# Digital_Port_F_Button.net
KiCad netlist of a schematic drawn in Altium Designer
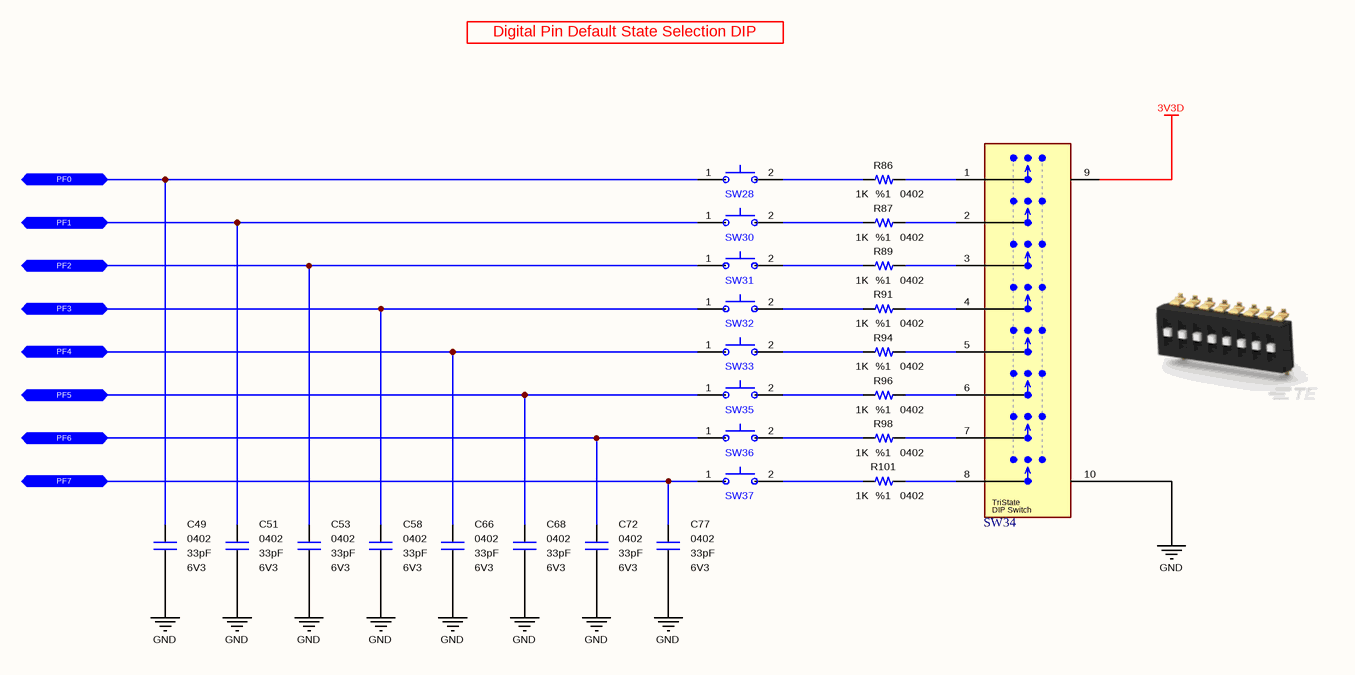
[diagram p0: Digital Port F Button.SchDoc]

(export (version "E")
  (design (tool "Eeschema 10.0.6"))
  (components
    (comp (ref "C49")
      (value "33pF")
      (footprint "CAPACITOR_0402")
      (description "Capacitor - 33pF [0402] (Ceramic)")
      (fields
        (field (name "MANUFACTURER PART NUMBER") "C0402C330J9RACAUTO")
        (field (name "MOUSER PART NUMBER") "80-C0402C330J9RAUTO")
        (field (name "CASE") "0402")
        (field (name "VOLTAGE") "6V3")
      )
      (libsource (lib "Ovoo_Library") (part "Capacitor - 33pF [0402-6V3]"))
    )
    (comp (ref "C51")
      (value "33pF")
      (footprint "CAPACITOR_0402")
      (description "Capacitor - 33pF [0402] (Ceramic)")
      (fields
        (field (name "MANUFACTURER PART NUMBER") "C0402C330J9RACAUTO")
        (field (name "MOUSER PART NUMBER") "80-C0402C330J9RAUTO")
        (field (name "CASE") "0402")
        (field (name "VOLTAGE") "6V3")
      )
      (libsource (lib "Ovoo_Library") (part "Capacitor - 33pF [0402-6V3]"))
    )
    (comp (ref "C53")
      (value "33pF")
      (footprint "CAPACITOR_0402")
      (description "Capacitor - 33pF [0402] (Ceramic)")
      (fields
        (field (name "MANUFACTURER PART NUMBER") "C0402C330J9RACAUTO")
        (field (name "MOUSER PART NUMBER") "80-C0402C330J9RAUTO")
        (field (name "CASE") "0402")
        (field (name "VOLTAGE") "6V3")
      )
      (libsource (lib "Ovoo_Library") (part "Capacitor - 33pF [0402-6V3]"))
    )
    (comp (ref "C58")
      (value "33pF")
      (footprint "CAPACITOR_0402")
      (description "Capacitor - 33pF [0402] (Ceramic)")
      (fields
        (field (name "MANUFACTURER PART NUMBER") "C0402C330J9RACAUTO")
        (field (name "MOUSER PART NUMBER") "80-C0402C330J9RAUTO")
        (field (name "CASE") "0402")
        (field (name "VOLTAGE") "6V3")
      )
      (libsource (lib "Ovoo_Library") (part "Capacitor - 33pF [0402-6V3]"))
    )
    (comp (ref "C66")
      (value "33pF")
      (footprint "CAPACITOR_0402")
      (description "Capacitor - 33pF [0402] (Ceramic)")
      (fields
        (field (name "MANUFACTURER PART NUMBER") "C0402C330J9RACAUTO")
        (field (name "MOUSER PART NUMBER") "80-C0402C330J9RAUTO")
        (field (name "CASE") "0402")
        (field (name "VOLTAGE") "6V3")
      )
      (libsource (lib "Ovoo_Library") (part "Capacitor - 33pF [0402-6V3]"))
    )
    (comp (ref "C68")
      (value "33pF")
      (footprint "CAPACITOR_0402")
      (description "Capacitor - 33pF [0402] (Ceramic)")
      (fields
        (field (name "MANUFACTURER PART NUMBER") "C0402C330J9RACAUTO")
        (field (name "MOUSER PART NUMBER") "80-C0402C330J9RAUTO")
        (field (name "CASE") "0402")
        (field (name "VOLTAGE") "6V3")
      )
      (libsource (lib "Ovoo_Library") (part "Capacitor - 33pF [0402-6V3]"))
    )
    (comp (ref "C72")
      (value "33pF")
      (footprint "CAPACITOR_0402")
      (description "Capacitor - 33pF [0402] (Ceramic)")
      (fields
        (field (name "MANUFACTURER PART NUMBER") "C0402C330J9RACAUTO")
        (field (name "MOUSER PART NUMBER") "80-C0402C330J9RAUTO")
        (field (name "CASE") "0402")
        (field (name "VOLTAGE") "6V3")
      )
      (libsource (lib "Ovoo_Library") (part "Capacitor - 33pF [0402-6V3]"))
    )
    (comp (ref "C77")
      (value "33pF")
      (footprint "CAPACITOR_0402")
      (description "Capacitor - 33pF [0402] (Ceramic)")
      (fields
        (field (name "MANUFACTURER PART NUMBER") "C0402C330J9RACAUTO")
        (field (name "MOUSER PART NUMBER") "80-C0402C330J9RAUTO")
        (field (name "CASE") "0402")
        (field (name "VOLTAGE") "6V3")
      )
      (libsource (lib "Ovoo_Library") (part "Capacitor - 33pF [0402-6V3]"))
    )
    (comp (ref "R86")
      (value "1K")
      (footprint "RESISTOR_0402")
      (description "Thick Film Resistors - SMD 1/16 W 1.0 Kohms 1%")
      (fields
        (field (name "MANUFACTURER PART NUMBER") "CRCW04021K00FKED")
        (field (name "MOUSER PART NUMBER") "71-CRCW0402-1.0K-E3")
        (field (name "TOLERANCE") "%1")
        (field (name "CASE") "0402")
      )
      (libsource (lib "Ovoo_Library") (part "Resistor - 1K"))
    )
    (comp (ref "R87")
      (value "1K")
      (footprint "RESISTOR_0402")
      (description "Thick Film Resistors - SMD 1/16 W 1.0 Kohms 1%")
      (fields
        (field (name "MANUFACTURER PART NUMBER") "CRCW04021K00FKED")
        (field (name "MOUSER PART NUMBER") "71-CRCW0402-1.0K-E3")
        (field (name "TOLERANCE") "%1")
        (field (name "CASE") "0402")
      )
      (libsource (lib "Ovoo_Library") (part "Resistor - 1K"))
    )
    (comp (ref "R89")
      (value "1K")
      (footprint "RESISTOR_0402")
      (description "Thick Film Resistors - SMD 1/16 W 1.0 Kohms 1%")
      (fields
        (field (name "MANUFACTURER PART NUMBER") "CRCW04021K00FKED")
        (field (name "MOUSER PART NUMBER") "71-CRCW0402-1.0K-E3")
        (field (name "TOLERANCE") "%1")
        (field (name "CASE") "0402")
      )
      (libsource (lib "Ovoo_Library") (part "Resistor - 1K"))
    )
    (comp (ref "R91")
      (value "1K")
      (footprint "RESISTOR_0402")
      (description "Thick Film Resistors - SMD 1/16 W 1.0 Kohms 1%")
      (fields
        (field (name "MANUFACTURER PART NUMBER") "CRCW04021K00FKED")
        (field (name "MOUSER PART NUMBER") "71-CRCW0402-1.0K-E3")
        (field (name "TOLERANCE") "%1")
        (field (name "CASE") "0402")
      )
      (libsource (lib "Ovoo_Library") (part "Resistor - 1K"))
    )
    (comp (ref "R94")
      (value "1K")
      (footprint "RESISTOR_0402")
      (description "Thick Film Resistors - SMD 1/16 W 1.0 Kohms 1%")
      (fields
        (field (name "MANUFACTURER PART NUMBER") "CRCW04021K00FKED")
        (field (name "MOUSER PART NUMBER") "71-CRCW0402-1.0K-E3")
        (field (name "TOLERANCE") "%1")
        (field (name "CASE") "0402")
      )
      (libsource (lib "Ovoo_Library") (part "Resistor - 1K"))
    )
    (comp (ref "R96")
      (value "1K")
      (footprint "RESISTOR_0402")
      (description "Thick Film Resistors - SMD 1/16 W 1.0 Kohms 1%")
      (fields
        (field (name "MANUFACTURER PART NUMBER") "CRCW04021K00FKED")
        (field (name "MOUSER PART NUMBER") "71-CRCW0402-1.0K-E3")
        (field (name "TOLERANCE") "%1")
        (field (name "CASE") "0402")
      )
      (libsource (lib "Ovoo_Library") (part "Resistor - 1K"))
    )
    (comp (ref "R98")
      (value "1K")
      (footprint "RESISTOR_0402")
      (description "Thick Film Resistors - SMD 1/16 W 1.0 Kohms 1%")
      (fields
        (field (name "MANUFACTURER PART NUMBER") "CRCW04021K00FKED")
        (field (name "MOUSER PART NUMBER") "71-CRCW0402-1.0K-E3")
        (field (name "TOLERANCE") "%1")
        (field (name "CASE") "0402")
      )
      (libsource (lib "Ovoo_Library") (part "Resistor - 1K"))
    )
    (comp (ref "R101")
      (value "1K")
      (footprint "RESISTOR_0402")
      (description "Thick Film Resistors - SMD 1/16 W 1.0 Kohms 1%")
      (fields
        (field (name "MANUFACTURER PART NUMBER") "CRCW04021K00FKED")
        (field (name "MOUSER PART NUMBER") "71-CRCW0402-1.0K-E3")
        (field (name "TOLERANCE") "%1")
        (field (name "CASE") "0402")
      )
      (libsource (lib "Ovoo_Library") (part "Resistor - 1K"))
    )
    (comp (ref "SW28")
      (value "Tactile Switches")
      (footprint "PTS526_Switch")
      (description "Tactile Switches 50mA 12VDC, 5.2x5.2mm, 0.8mm H, 260gf, G leads.")
      (fields
        (field (name "MANUFACTURER PART NUMBER") "PTS526 SK08 SMTR2 LFS")
        (field (name "MOUSER PART NUMBER") "611-PTS526SK08SMTR2L")
      )
      (libsource (lib "Ovoo_Library") (part "Switch - Tactile"))
    )
    (comp (ref "SW30")
      (value "Tactile Switches")
      (footprint "PTS526_Switch")
      (description "Tactile Switches 50mA 12VDC, 5.2x5.2mm, 0.8mm H, 260gf, G leads.")
      (fields
        (field (name "MANUFACTURER PART NUMBER") "PTS526 SK08 SMTR2 LFS")
        (field (name "MOUSER PART NUMBER") "611-PTS526SK08SMTR2L")
      )
      (libsource (lib "Ovoo_Library") (part "Switch - Tactile"))
    )
    (comp (ref "SW31")
      (value "Tactile Switches")
      (footprint "PTS526_Switch")
      (description "Tactile Switches 50mA 12VDC, 5.2x5.2mm, 0.8mm H, 260gf, G leads.")
      (fields
        (field (name "MANUFACTURER PART NUMBER") "PTS526 SK08 SMTR2 LFS")
        (field (name "MOUSER PART NUMBER") "611-PTS526SK08SMTR2L")
      )
      (libsource (lib "Ovoo_Library") (part "Switch - Tactile"))
    )
    (comp (ref "SW32")
      (value "Tactile Switches")
      (footprint "PTS526_Switch")
      (description "Tactile Switches 50mA 12VDC, 5.2x5.2mm, 0.8mm H, 260gf, G leads.")
      (fields
        (field (name "MANUFACTURER PART NUMBER") "PTS526 SK08 SMTR2 LFS")
        (field (name "MOUSER PART NUMBER") "611-PTS526SK08SMTR2L")
      )
      (libsource (lib "Ovoo_Library") (part "Switch - Tactile"))
    )
    (comp (ref "SW33")
      (value "Tactile Switches")
      (footprint "PTS526_Switch")
      (description "Tactile Switches 50mA 12VDC, 5.2x5.2mm, 0.8mm H, 260gf, G leads.")
      (fields
        (field (name "MANUFACTURER PART NUMBER") "PTS526 SK08 SMTR2 LFS")
        (field (name "MOUSER PART NUMBER") "611-PTS526SK08SMTR2L")
      )
      (libsource (lib "Ovoo_Library") (part "Switch - Tactile"))
    )
    (comp (ref "SW34")
      (value "DIP Switches/SIP Switches")
      (footprint "TDS08SGNNTR04")
      (description "DIP Switches/SIP Switches TRI-STATE DIP 8P G RAISED T&R")
      (fields
        (field (name "MANUFACTURER PART NUMBER") "TDS08SGNNTR04")
        (field (name "MOUSER PART NUMBER") "506-TDS08SGNNTR04")
      )
      (libsource (lib "Ovoo_Library") (part "Switch - DIP Switch (8 Pole TriState)"))
    )
    (comp (ref "SW35")
      (value "Tactile Switches")
      (footprint "PTS526_Switch")
      (description "Tactile Switches 50mA 12VDC, 5.2x5.2mm, 0.8mm H, 260gf, G leads.")
      (fields
        (field (name "MANUFACTURER PART NUMBER") "PTS526 SK08 SMTR2 LFS")
        (field (name "MOUSER PART NUMBER") "611-PTS526SK08SMTR2L")
      )
      (libsource (lib "Ovoo_Library") (part "Switch - Tactile"))
    )
    (comp (ref "SW36")
      (value "Tactile Switches")
      (footprint "PTS526_Switch")
      (description "Tactile Switches 50mA 12VDC, 5.2x5.2mm, 0.8mm H, 260gf, G leads.")
      (fields
        (field (name "MANUFACTURER PART NUMBER") "PTS526 SK08 SMTR2 LFS")
        (field (name "MOUSER PART NUMBER") "611-PTS526SK08SMTR2L")
      )
      (libsource (lib "Ovoo_Library") (part "Switch - Tactile"))
    )
    (comp (ref "SW37")
      (value "Tactile Switches")
      (footprint "PTS526_Switch")
      (description "Tactile Switches 50mA 12VDC, 5.2x5.2mm, 0.8mm H, 260gf, G leads.")
      (fields
        (field (name "MANUFACTURER PART NUMBER") "PTS526 SK08 SMTR2 LFS")
        (field (name "MOUSER PART NUMBER") "611-PTS526SK08SMTR2L")
      )
      (libsource (lib "Ovoo_Library") (part "Switch - Tactile"))
    )
  )
  (nets
    (net (code "1") (name "/PF0") (class "Default")
      (node (ref "C49") (pin "2") (pinfunction "2_2") (pintype "passive"))
      (node (ref "SW28") (pin "1") (pinfunction "NC_1") (pintype "passive"))
    )
    (net (code "2") (name "/PF1") (class "Default")
      (node (ref "C51") (pin "2") (pinfunction "2_2") (pintype "passive"))
      (node (ref "SW30") (pin "1") (pinfunction "NC_1") (pintype "passive"))
    )
    (net (code "3") (name "/PF2") (class "Default")
      (node (ref "C53") (pin "2") (pinfunction "2_2") (pintype "passive"))
      (node (ref "SW31") (pin "1") (pinfunction "NC_1") (pintype "passive"))
    )
    (net (code "4") (name "/PF3") (class "Default")
      (node (ref "C58") (pin "2") (pinfunction "2_2") (pintype "passive"))
      (node (ref "SW32") (pin "1") (pinfunction "NC_1") (pintype "passive"))
    )
    (net (code "5") (name "/PF4") (class "Default")
      (node (ref "C66") (pin "2") (pinfunction "2_2") (pintype "passive"))
      (node (ref "SW33") (pin "1") (pinfunction "NC_1") (pintype "passive"))
    )
    (net (code "6") (name "/PF5") (class "Default")
      (node (ref "C68") (pin "2") (pinfunction "2_2") (pintype "passive"))
      (node (ref "SW35") (pin "1") (pinfunction "NC_1") (pintype "passive"))
    )
    (net (code "7") (name "/PF6") (class "Default")
      (node (ref "C72") (pin "2") (pinfunction "2_2") (pintype "passive"))
      (node (ref "SW36") (pin "1") (pinfunction "NC_1") (pintype "passive"))
    )
    (net (code "8") (name "/PF7") (class "Default")
      (node (ref "C77") (pin "2") (pinfunction "2_2") (pintype "passive"))
      (node (ref "SW37") (pin "1") (pinfunction "NC_1") (pintype "passive"))
    )
    (net (code "9") (name "3V3D") (class "Default")
      (node (ref "SW34") (pin "9") (pinfunction "VCC_9") (pintype "passive"))
    )
    (net (code "10") (name "GND") (class "Default")
      (node (ref "C49") (pin "1") (pinfunction "1_1") (pintype "passive"))
      (node (ref "C51") (pin "1") (pinfunction "1_1") (pintype "passive"))
      (node (ref "C53") (pin "1") (pinfunction "1_1") (pintype "passive"))
      (node (ref "C58") (pin "1") (pinfunction "1_1") (pintype "passive"))
      (node (ref "C66") (pin "1") (pinfunction "1_1") (pintype "passive"))
      (node (ref "C68") (pin "1") (pinfunction "1_1") (pintype "passive"))
      (node (ref "C72") (pin "1") (pinfunction "1_1") (pintype "passive"))
      (node (ref "C77") (pin "1") (pinfunction "1_1") (pintype "passive"))
      (node (ref "SW34") (pin "10") (pinfunction "GND_10") (pintype "passive"))
    )
    (net (code "11") (name "Net-(R86-Pad1)") (class "Default")
      (node (ref "R86") (pin "1") (pinfunction "1_1") (pintype "passive"))
      (node (ref "SW34") (pin "1") (pinfunction "1_1") (pintype "passive"))
    )
    (net (code "12") (name "Net-(R87-Pad1)") (class "Default")
      (node (ref "R87") (pin "1") (pinfunction "1_1") (pintype "passive"))
      (node (ref "SW34") (pin "2") (pinfunction "2_2") (pintype "passive"))
    )
    (net (code "13") (name "Net-(R89-Pad1)") (class "Default")
      (node (ref "R89") (pin "1") (pinfunction "1_1") (pintype "passive"))
      (node (ref "SW34") (pin "3") (pinfunction "3_3") (pintype "passive"))
    )
    (net (code "14") (name "Net-(R91-Pad1)") (class "Default")
      (node (ref "R91") (pin "1") (pinfunction "1_1") (pintype "passive"))
      (node (ref "SW34") (pin "4") (pinfunction "4_4") (pintype "passive"))
    )
    (net (code "15") (name "Net-(R94-Pad1)") (class "Default")
      (node (ref "R94") (pin "1") (pinfunction "1_1") (pintype "passive"))
      (node (ref "SW34") (pin "5") (pinfunction "5_5") (pintype "passive"))
    )
    (net (code "16") (name "Net-(R96-Pad1)") (class "Default")
      (node (ref "R96") (pin "1") (pinfunction "1_1") (pintype "passive"))
      (node (ref "SW34") (pin "6") (pinfunction "6_6") (pintype "passive"))
    )
    (net (code "17") (name "Net-(R98-Pad1)") (class "Default")
      (node (ref "R98") (pin "1") (pinfunction "1_1") (pintype "passive"))
      (node (ref "SW34") (pin "7") (pinfunction "7_7") (pintype "passive"))
    )
    (net (code "18") (name "Net-(R101-Pad1)") (class "Default")
      (node (ref "R101") (pin "1") (pinfunction "1_1") (pintype "passive"))
      (node (ref "SW34") (pin "8") (pinfunction "8_8") (pintype "passive"))
    )
    (net (code "19") (name "Net-(SW28-COM)") (class "Default")
      (node (ref "R86") (pin "2") (pinfunction "2_2") (pintype "passive"))
      (node (ref "SW28") (pin "2") (pinfunction "COM_2") (pintype "passive"))
    )
    (net (code "20") (name "Net-(SW30-COM)") (class "Default")
      (node (ref "R87") (pin "2") (pinfunction "2_2") (pintype "passive"))
      (node (ref "SW30") (pin "2") (pinfunction "COM_2") (pintype "passive"))
    )
    (net (code "21") (name "Net-(SW31-COM)") (class "Default")
      (node (ref "R89") (pin "2") (pinfunction "2_2") (pintype "passive"))
      (node (ref "SW31") (pin "2") (pinfunction "COM_2") (pintype "passive"))
    )
    (net (code "22") (name "Net-(SW32-COM)") (class "Default")
      (node (ref "R91") (pin "2") (pinfunction "2_2") (pintype "passive"))
      (node (ref "SW32") (pin "2") (pinfunction "COM_2") (pintype "passive"))
    )
    (net (code "23") (name "Net-(SW33-COM)") (class "Default")
      (node (ref "R94") (pin "2") (pinfunction "2_2") (pintype "passive"))
      (node (ref "SW33") (pin "2") (pinfunction "COM_2") (pintype "passive"))
    )
    (net (code "24") (name "Net-(SW35-COM)") (class "Default")
      (node (ref "R96") (pin "2") (pinfunction "2_2") (pintype "passive"))
      (node (ref "SW35") (pin "2") (pinfunction "COM_2") (pintype "passive"))
    )
    (net (code "25") (name "Net-(SW36-COM)") (class "Default")
      (node (ref "R98") (pin "2") (pinfunction "2_2") (pintype "passive"))
      (node (ref "SW36") (pin "2") (pinfunction "COM_2") (pintype "passive"))
    )
    (net (code "26") (name "Net-(SW37-COM)") (class "Default")
      (node (ref "R101") (pin "2") (pinfunction "2_2") (pintype "passive"))
      (node (ref "SW37") (pin "2") (pinfunction "COM_2") (pintype "passive"))
    )
  )
)
